# FreedomWing1_1.net
KiCad netlist of a schematic drawn in EAGLE
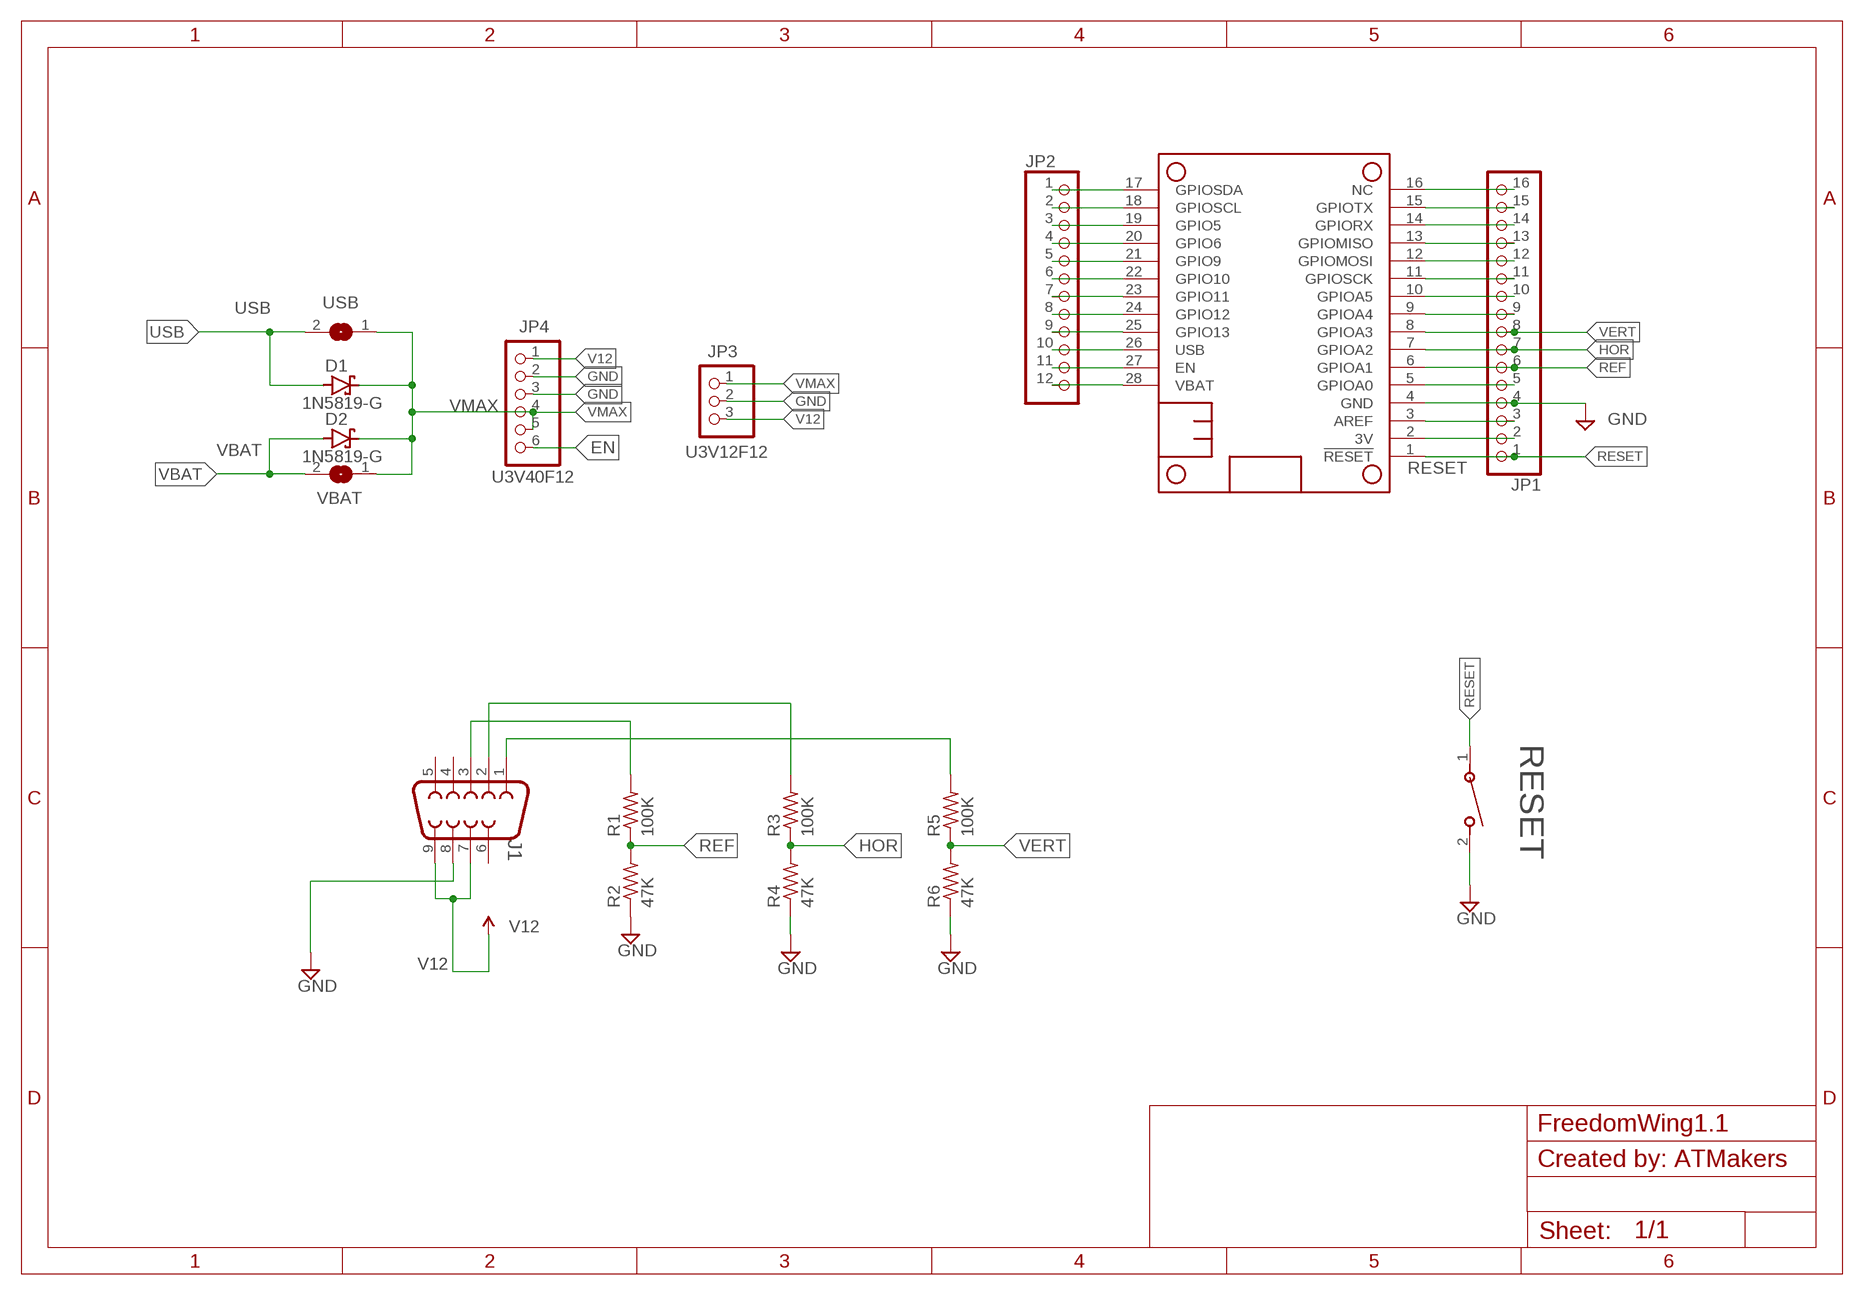
[diagram p0: schematic, sheet 1]

(export (version "E")
  (design (tool "Eeschema 10.0.6"))
  (components
    (comp (ref "D1")
      (value "1N5819-G")
      (footprint "eagle-import:DO41-7")
      (libsource (lib "eagle-import") (part "1N5819-G"))
    )
    (comp (ref "D2")
      (value "1N5819-G")
      (footprint "eagle-import:DO41-7")
      (libsource (lib "eagle-import") (part "1N5819-G"))
    )
    (comp (ref "J1")
      (value "5747844-4")
      (footprint "eagle-import:DB9_CONNECTOR_MALE")
      (libsource (lib "eagle-import") (part "DB9_CONNECTOR-MALE"))
    )
    (comp (ref "JP1")
      (value "PINHD-1X16")
      (footprint "eagle-import:1X16")
      (libsource (lib "eagle-import") (part "PINHD-1X16"))
    )
    (comp (ref "JP2")
      (value "PINHD-1X12")
      (footprint "eagle-import:1X12")
      (libsource (lib "eagle-import") (part "PINHD-1X12"))
    )
    (comp (ref "JP3")
      (value "U3V12F12")
      (footprint "eagle-import:1X03")
      (libsource (lib "eagle-import") (part "PINHD-1X3"))
    )
    (comp (ref "JP4")
      (value "U3V40F12")
      (footprint "eagle-import:1X06")
      (libsource (lib "eagle-import") (part "PINHD-1X6"))
    )
    (comp (ref "MS1")
      (value "ADAFRUIT_FEATHER_NODIM")
      (footprint "eagle-import:ADAFRUIT_FEATHERWING_DIM")
      (libsource (lib "eagle-import") (part "ADAFRUIT_FEATHER_NODIM"))
    )
    (comp (ref "R1")
      (value "100K")
      (footprint "eagle-import:RESISTOR_0207_10")
      (libsource (lib "eagle-import") (part "RESISTOR-US-0207/10"))
    )
    (comp (ref "R2")
      (value "47K")
      (footprint "eagle-import:RESISTOR_0207_10")
      (libsource (lib "eagle-import") (part "RESISTOR-US-0207/10"))
    )
    (comp (ref "R3")
      (value "100K")
      (footprint "eagle-import:RESISTOR_0207_10")
      (libsource (lib "eagle-import") (part "RESISTOR-US-0207/10"))
    )
    (comp (ref "R4")
      (value "47K")
      (footprint "eagle-import:RESISTOR_0207_10")
      (libsource (lib "eagle-import") (part "RESISTOR-US-0207/10"))
    )
    (comp (ref "R5")
      (value "100K")
      (footprint "eagle-import:RESISTOR_0207_10")
      (libsource (lib "eagle-import") (part "RESISTOR-US-0207/10"))
    )
    (comp (ref "R6")
      (value "47K")
      (footprint "eagle-import:RESISTOR_0207_10")
      (libsource (lib "eagle-import") (part "RESISTOR-US-0207/10"))
    )
    (comp (ref "RESET")
      (value "SWITCH_SPST-NO")
      (footprint "eagle-import:SWITCH_SPST-NO")
      (fields
        (field (name "MANUFACTURER_PART_NUMBER") "1825966-1")
        (field (name "COPYRIGHT") "Copyright (C) 2016 Accelerated Designs. All rights reserved")
      )
      (libsource (lib "eagle-import") (part "SWITCH_SPST-NO"))
    )
    (comp (ref "USB")
      (value "SJW")
      (footprint "eagle-import:SJW")
      (libsource (lib "eagle-import") (part "SJW"))
    )
    (comp (ref "VBAT")
      (value "SJW")
      (footprint "eagle-import:SJW")
      (libsource (lib "eagle-import") (part "SJW"))
    )
  )
  (nets
    (net (code "1") (name "EN") (class "Default")
      (node (ref "JP4") (pin "6") (pinfunction "6_6") (pintype "passive"))
    )
    (net (code "2") (name "GND") (class "Default")
      (node (ref "J1") (pin "8") (pinfunction "8_8") (pintype "passive"))
      (node (ref "JP1") (pin "4") (pinfunction "4_4") (pintype "passive"))
      (node (ref "JP3") (pin "2") (pinfunction "2_2") (pintype "passive"))
      (node (ref "JP4") (pin "2") (pinfunction "2_2") (pintype "passive"))
      (node (ref "JP4") (pin "3") (pinfunction "3_3") (pintype "passive"))
      (node (ref "MS1") (pin "4") (pinfunction "GND_4") (pintype "power_in"))
      (node (ref "R2") (pin "1") (pinfunction "1_1") (pintype "passive"))
      (node (ref "R4") (pin "1") (pinfunction "1_1") (pintype "passive"))
      (node (ref "R6") (pin "1") (pinfunction "1_1") (pintype "passive"))
      (node (ref "RESET") (pin "2") (pinfunction "2_2") (pintype "passive"))
    )
    (net (code "3") (name "HOR") (class "Default")
      (node (ref "JP1") (pin "7") (pinfunction "7_7") (pintype "passive"))
      (node (ref "MS1") (pin "7") (pinfunction "GPIOA2_7") (pintype "bidirectional"))
      (node (ref "R3") (pin "1") (pinfunction "1_1") (pintype "passive"))
      (node (ref "R4") (pin "2") (pinfunction "2_2") (pintype "passive"))
    )
    (net (code "4") (name "Net-(J1-Pad1)") (class "Default")
      (node (ref "J1") (pin "1") (pinfunction "1_1") (pintype "passive"))
      (node (ref "R5") (pin "2") (pinfunction "2_2") (pintype "passive"))
    )
    (net (code "5") (name "Net-(J1-Pad2)") (class "Default")
      (node (ref "J1") (pin "2") (pinfunction "2_2") (pintype "passive"))
      (node (ref "R3") (pin "2") (pinfunction "2_2") (pintype "passive"))
    )
    (net (code "6") (name "Net-(J1-Pad3)") (class "Default")
      (node (ref "J1") (pin "3") (pinfunction "3_3") (pintype "passive"))
      (node (ref "R1") (pin "2") (pinfunction "2_2") (pintype "passive"))
    )
    (net (code "7") (name "Net-(MS1-3V)") (class "Default")
      (node (ref "JP1") (pin "2") (pinfunction "2_2") (pintype "passive"))
      (node (ref "MS1") (pin "2") (pinfunction "3V_2") (pintype "power_in"))
    )
    (net (code "8") (name "Net-(MS1-AREF)") (class "Default")
      (node (ref "JP1") (pin "3") (pinfunction "3_3") (pintype "passive"))
      (node (ref "MS1") (pin "3") (pinfunction "AREF_3") (pintype "passive"))
    )
    (net (code "9") (name "Net-(MS1-EN)") (class "Default")
      (node (ref "JP2") (pin "11") (pinfunction "11_11") (pintype "passive"))
      (node (ref "MS1") (pin "27") (pinfunction "EN_27") (pintype "passive"))
    )
    (net (code "10") (name "Net-(MS1-GPIO5)") (class "Default")
      (node (ref "JP2") (pin "3") (pinfunction "3_3") (pintype "passive"))
      (node (ref "MS1") (pin "19") (pinfunction "GPIO5_19") (pintype "bidirectional"))
    )
    (net (code "11") (name "Net-(MS1-GPIO6)") (class "Default")
      (node (ref "JP2") (pin "4") (pinfunction "4_4") (pintype "passive"))
      (node (ref "MS1") (pin "20") (pinfunction "GPIO6_20") (pintype "bidirectional"))
    )
    (net (code "12") (name "Net-(MS1-GPIO9)") (class "Default")
      (node (ref "JP2") (pin "5") (pinfunction "5_5") (pintype "passive"))
      (node (ref "MS1") (pin "21") (pinfunction "GPIO9_21") (pintype "bidirectional"))
    )
    (net (code "13") (name "Net-(MS1-GPIO10)") (class "Default")
      (node (ref "JP2") (pin "6") (pinfunction "6_6") (pintype "passive"))
      (node (ref "MS1") (pin "22") (pinfunction "GPIO10_22") (pintype "bidirectional"))
    )
    (net (code "14") (name "Net-(MS1-GPIO11)") (class "Default")
      (node (ref "JP2") (pin "7") (pinfunction "7_7") (pintype "passive"))
      (node (ref "MS1") (pin "23") (pinfunction "GPIO11_23") (pintype "bidirectional"))
    )
    (net (code "15") (name "Net-(MS1-GPIO12)") (class "Default")
      (node (ref "JP2") (pin "8") (pinfunction "8_8") (pintype "passive"))
      (node (ref "MS1") (pin "24") (pinfunction "GPIO12_24") (pintype "bidirectional"))
    )
    (net (code "16") (name "Net-(MS1-GPIO13)") (class "Default")
      (node (ref "JP2") (pin "9") (pinfunction "9_9") (pintype "passive"))
      (node (ref "MS1") (pin "25") (pinfunction "GPIO13_25") (pintype "bidirectional"))
    )
    (net (code "17") (name "Net-(MS1-GPIOA0)") (class "Default")
      (node (ref "JP1") (pin "5") (pinfunction "5_5") (pintype "passive"))
      (node (ref "MS1") (pin "5") (pinfunction "GPIOA0_5") (pintype "bidirectional"))
    )
    (net (code "18") (name "Net-(MS1-GPIOA4)") (class "Default")
      (node (ref "JP1") (pin "9") (pinfunction "9_9") (pintype "passive"))
      (node (ref "MS1") (pin "9") (pinfunction "GPIOA4_9") (pintype "bidirectional"))
    )
    (net (code "19") (name "Net-(MS1-GPIOA5)") (class "Default")
      (node (ref "JP1") (pin "10") (pinfunction "10_10") (pintype "passive"))
      (node (ref "MS1") (pin "10") (pinfunction "GPIOA5_10") (pintype "bidirectional"))
    )
    (net (code "20") (name "Net-(MS1-GPIOMISO)") (class "Default")
      (node (ref "JP1") (pin "13") (pinfunction "13_13") (pintype "passive"))
      (node (ref "MS1") (pin "13") (pinfunction "GPIOMISO_13") (pintype "bidirectional"))
    )
    (net (code "21") (name "Net-(MS1-GPIOMOSI)") (class "Default")
      (node (ref "JP1") (pin "12") (pinfunction "12_12") (pintype "passive"))
      (node (ref "MS1") (pin "12") (pinfunction "GPIOMOSI_12") (pintype "bidirectional"))
    )
    (net (code "22") (name "Net-(MS1-GPIORX)") (class "Default")
      (node (ref "JP1") (pin "14") (pinfunction "14_14") (pintype "passive"))
      (node (ref "MS1") (pin "14") (pinfunction "GPIORX_14") (pintype "bidirectional"))
    )
    (net (code "23") (name "Net-(MS1-GPIOSCK)") (class "Default")
      (node (ref "JP1") (pin "11") (pinfunction "11_11") (pintype "passive"))
      (node (ref "MS1") (pin "11") (pinfunction "GPIOSCK_11") (pintype "bidirectional"))
    )
    (net (code "24") (name "Net-(MS1-GPIOSCL)") (class "Default")
      (node (ref "JP2") (pin "2") (pinfunction "2_2") (pintype "passive"))
      (node (ref "MS1") (pin "18") (pinfunction "GPIOSCL_18") (pintype "bidirectional"))
    )
    (net (code "25") (name "Net-(MS1-GPIOSDA)") (class "Default")
      (node (ref "JP2") (pin "1") (pinfunction "1_1") (pintype "passive"))
      (node (ref "MS1") (pin "17") (pinfunction "GPIOSDA_17") (pintype "bidirectional"))
    )
    (net (code "26") (name "Net-(MS1-GPIOTX)") (class "Default")
      (node (ref "JP1") (pin "15") (pinfunction "15_15") (pintype "passive"))
      (node (ref "MS1") (pin "15") (pinfunction "GPIOTX_15") (pintype "bidirectional"))
    )
    (net (code "27") (name "Net-(MS1-NC)") (class "Default")
      (node (ref "JP1") (pin "16") (pinfunction "16_16") (pintype "passive"))
      (node (ref "MS1") (pin "16") (pinfunction "NC_16") (pintype "passive"))
    )
    (net (code "28") (name "REF") (class "Default")
      (node (ref "JP1") (pin "6") (pinfunction "6_6") (pintype "passive"))
      (node (ref "MS1") (pin "6") (pinfunction "GPIOA1_6") (pintype "bidirectional"))
      (node (ref "R1") (pin "1") (pinfunction "1_1") (pintype "passive"))
      (node (ref "R2") (pin "2") (pinfunction "2_2") (pintype "passive"))
    )
    (net (code "29") (name "RESET") (class "Default")
      (node (ref "JP1") (pin "1") (pinfunction "1_1") (pintype "passive"))
      (node (ref "MS1") (pin "1") (pinfunction "~{RESET}_1") (pintype "input"))
      (node (ref "RESET") (pin "1") (pinfunction "1_1") (pintype "passive"))
    )
    (net (code "30") (name "USB") (class "Default")
      (node (ref "D1") (pin "A") (pinfunction "A_A") (pintype "passive"))
      (node (ref "JP2") (pin "10") (pinfunction "10_10") (pintype "passive"))
      (node (ref "MS1") (pin "26") (pinfunction "USB_26") (pintype "power_in"))
      (node (ref "USB") (pin "2") (pinfunction "2_2") (pintype "passive"))
    )
    (net (code "31") (name "V12") (class "Default")
      (node (ref "J1") (pin "7") (pinfunction "7_7") (pintype "passive"))
      (node (ref "J1") (pin "9") (pinfunction "9_9") (pintype "passive"))
      (node (ref "JP3") (pin "3") (pinfunction "3_3") (pintype "passive"))
      (node (ref "JP4") (pin "1") (pinfunction "1_1") (pintype "passive"))
    )
    (net (code "32") (name "VBAT") (class "Default")
      (node (ref "D2") (pin "A") (pinfunction "A_A") (pintype "passive"))
      (node (ref "JP2") (pin "12") (pinfunction "12_12") (pintype "passive"))
      (node (ref "MS1") (pin "28") (pinfunction "VBAT_28") (pintype "power_in"))
      (node (ref "VBAT") (pin "2") (pinfunction "2_2") (pintype "passive"))
    )
    (net (code "33") (name "VERT") (class "Default")
      (node (ref "JP1") (pin "8") (pinfunction "8_8") (pintype "passive"))
      (node (ref "MS1") (pin "8") (pinfunction "GPIOA3_8") (pintype "bidirectional"))
      (node (ref "R5") (pin "1") (pinfunction "1_1") (pintype "passive"))
      (node (ref "R6") (pin "2") (pinfunction "2_2") (pintype "passive"))
    )
    (net (code "34") (name "VMAX") (class "Default")
      (node (ref "D1") (pin "C") (pinfunction "C_C") (pintype "passive"))
      (node (ref "D2") (pin "C") (pinfunction "C_C") (pintype "passive"))
      (node (ref "JP3") (pin "1") (pinfunction "1_1") (pintype "passive"))
      (node (ref "JP4") (pin "4") (pinfunction "4_4") (pintype "passive"))
      (node (ref "JP4") (pin "5") (pinfunction "5_5") (pintype "passive"))
      (node (ref "USB") (pin "1") (pinfunction "1_1") (pintype "passive"))
      (node (ref "VBAT") (pin "1") (pinfunction "1_1") (pintype "passive"))
    )
    (net (code "35") (name "unconnected-(J1-Pad4)") (class "Default")
      (node (ref "J1") (pin "4") (pinfunction "4_4") (pintype "passive"))
    )
    (net (code "36") (name "unconnected-(J1-Pad5)") (class "Default")
      (node (ref "J1") (pin "5") (pinfunction "5_5") (pintype "passive"))
    )
    (net (code "37") (name "unconnected-(J1-Pad6)") (class "Default")
      (node (ref "J1") (pin "6") (pinfunction "6_6") (pintype "passive"))
    )
  )
)
